# S7_SDRAM.net
KiCad netlist of a schematic drawn in Altium Designer
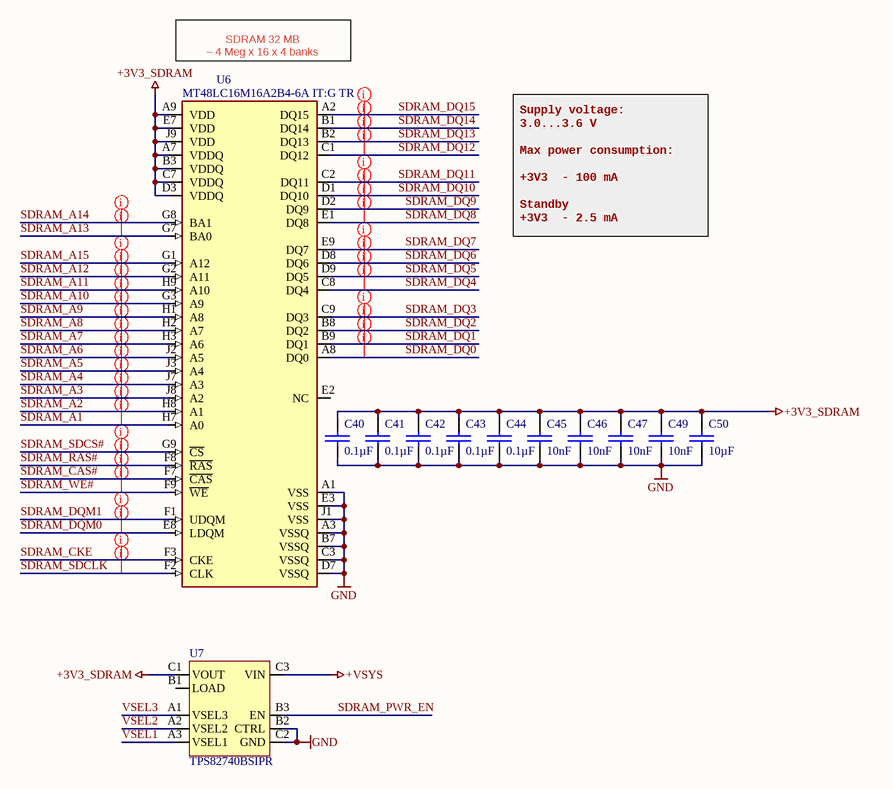
[diagram p0: S7_SDRAM.SchDoc]

(export (version "E")
  (design (tool "Eeschema 10.0.6"))
  (components
    (comp (ref "C40")
      (value "0.1µF")
      (footprint "0402 CAP")
      (description "0.1µF, ±10%, 50V, X7R, 0402 (1005 Metric), -55°C ~ 125°C, -, General Purpose")
      (fields
        (field (name "PART NUMBER") "0402B104K500CT")
        (field (name "MANUFACTURER") "Walsin Technology Corporation")
      )
      (libsource (lib "ea_PassivComps") (part "Capacitor"))
    )
    (comp (ref "C41")
      (value "0.1µF")
      (footprint "0402 CAP")
      (description "0.1µF, ±10%, 50V, X7R, 0402 (1005 Metric), -55°C ~ 125°C, -, General Purpose")
      (fields
        (field (name "PART NUMBER") "0402B104K500CT")
        (field (name "MANUFACTURER") "Walsin Technology Corporation")
      )
      (libsource (lib "ea_PassivComps") (part "Capacitor"))
    )
    (comp (ref "C42")
      (value "0.1µF")
      (footprint "0402 CAP")
      (description "0.1µF, ±10%, 50V, X7R, 0402 (1005 Metric), -55°C ~ 125°C, -, General Purpose")
      (fields
        (field (name "PART NUMBER") "0402B104K500CT")
        (field (name "MANUFACTURER") "Walsin Technology Corporation")
      )
      (libsource (lib "ea_PassivComps") (part "Capacitor"))
    )
    (comp (ref "C43")
      (value "0.1µF")
      (footprint "0402 CAP")
      (description "0.1µF, ±10%, 50V, X7R, 0402 (1005 Metric), -55°C ~ 125°C, -, General Purpose")
      (fields
        (field (name "PART NUMBER") "0402B104K500CT")
        (field (name "MANUFACTURER") "Walsin Technology Corporation")
      )
      (libsource (lib "ea_PassivComps") (part "Capacitor"))
    )
    (comp (ref "C44")
      (value "0.1µF")
      (footprint "0402 CAP")
      (description "0.1µF, ±10%, 50V, X7R, 0402 (1005 Metric), -55°C ~ 125°C, -, General Purpose")
      (fields
        (field (name "PART NUMBER") "0402B104K500CT")
        (field (name "MANUFACTURER") "Walsin Technology Corporation")
      )
      (libsource (lib "ea_PassivComps") (part "Capacitor"))
    )
    (comp (ref "C45")
      (value "10nF")
      (footprint "0402 CAP")
      (description "10000pF, ±10%, 50V, X7R, 0402 (1005 Metric), -55°C ~ 125°C, -, General Purpose")
      (fields
        (field (name "PART NUMBER") "CL05B103KB5NNNC")
        (field (name "MANUFACTURER") "Samsung Electro-Mechanics")
      )
      (libsource (lib "ea_PassivComps") (part "Capacitor"))
    )
    (comp (ref "C46")
      (value "10nF")
      (footprint "0402 CAP")
      (description "10000pF, ±10%, 50V, X7R, 0402 (1005 Metric), -55°C ~ 125°C, -, General Purpose")
      (fields
        (field (name "PART NUMBER") "CL05B103KB5NNNC")
        (field (name "MANUFACTURER") "Samsung Electro-Mechanics")
      )
      (libsource (lib "ea_PassivComps") (part "Capacitor"))
    )
    (comp (ref "C47")
      (value "10nF")
      (footprint "0402 CAP")
      (description "10000pF, ±10%, 50V, X7R, 0402 (1005 Metric), -55°C ~ 125°C, -, General Purpose")
      (fields
        (field (name "PART NUMBER") "CL05B103KB5NNNC")
        (field (name "MANUFACTURER") "Samsung Electro-Mechanics")
      )
      (libsource (lib "ea_PassivComps") (part "Capacitor"))
    )
    (comp (ref "C49")
      (value "10nF")
      (footprint "0402 CAP")
      (description "10000pF, ±10%, 50V, X7R, 0402 (1005 Metric), -55°C ~ 125°C, -, General Purpose")
      (fields
        (field (name "PART NUMBER") "CL05B103KB5NNNC")
        (field (name "MANUFACTURER") "Samsung Electro-Mechanics")
      )
      (libsource (lib "ea_PassivComps") (part "Capacitor"))
    )
    (comp (ref "C50")
      (value "10µF")
      (footprint "0603 CAP")
      (description "10µF, ±10%, 16V, X5R, 0603 (1608 Metric), -55°C ~ 85°C, -, Automotive")
      (fields
        (field (name "PART NUMBER") "GRT188R61C106KE13D")
        (field (name "MANUFACTURER") "Murata Electronics North America")
      )
      (libsource (lib "ea_PassivComps") (part "Capacitor"))
    )
    (comp (ref "U6")
      (value "MT48LC16M16A2B4-6A IT:G TR")
      (footprint "MICRON_VFBGA54")
      (description "Micron SDRAM 256M-Bit 16Mx16, 3.3V, 167MHz, 6ns, -40°C ~ +85°C, 54-VFBGA (8x8) Pb-free")
      (fields
        (field (name "MANUFACTURER") "Micron Technology Inc.")
        (field (name "PARTNUM") "340-128306-REEL")
      )
      (libsource (lib "ea_IC_RAM") (part "MT48LC16M16A2B4-6A IT{colon}G TR"))
    )
    (comp (ref "U7")
      (value "TPS82740BSIPR")
      (footprint "MicroSiP")
      (fields (field (name "MANUFACTURER") "Texas Instruments") (field (name "PARTNUM") "296-46481-1-ND"))
      (libsource (lib "ea_IC_Power_Reg_Ref_Sw") (part "TPS82740BSIPR"))
    )
  )
  (nets
    (net (code "1") (name "+3V3_SDRAM") (class "Default")
      (node (ref "C40") (pin "1") (pinfunction "1_1") (pintype "passive"))
      (node (ref "C41") (pin "1") (pinfunction "1_1") (pintype "passive"))
      (node (ref "C42") (pin "1") (pinfunction "1_1") (pintype "passive"))
      (node (ref "C43") (pin "1") (pinfunction "1_1") (pintype "passive"))
      (node (ref "C44") (pin "1") (pinfunction "1_1") (pintype "passive"))
      (node (ref "C45") (pin "1") (pinfunction "1_1") (pintype "passive"))
      (node (ref "C46") (pin "1") (pinfunction "1_1") (pintype "passive"))
      (node (ref "C47") (pin "1") (pinfunction "1_1") (pintype "passive"))
      (node (ref "C49") (pin "1") (pinfunction "1_1") (pintype "passive"))
      (node (ref "C50") (pin "1") (pinfunction "1_1") (pintype "passive"))
      (node (ref "U6") (pin "A7") (pinfunction "VDDQ_A7") (pintype "power_in"))
      (node (ref "U6") (pin "A9") (pinfunction "VDD_A9") (pintype "power_in"))
      (node (ref "U6") (pin "B3") (pinfunction "VDDQ_B3") (pintype "power_in"))
      (node (ref "U6") (pin "C7") (pinfunction "VDDQ_C7") (pintype "power_in"))
      (node (ref "U6") (pin "D3") (pinfunction "VDDQ_D3") (pintype "power_in"))
      (node (ref "U6") (pin "E7") (pinfunction "VDD_E7") (pintype "power_in"))
      (node (ref "U6") (pin "J9") (pinfunction "VDD_J9") (pintype "power_in"))
      (node (ref "U7") (pin "C1") (pinfunction "VOUT_C1") (pintype "passive"))
    )
    (net (code "2") (name "+VSYS") (class "Default")
      (node (ref "U7") (pin "C3") (pinfunction "VIN_C3") (pintype "passive"))
    )
    (net (code "3") (name "/SDRAM_A1") (class "Default")
      (node (ref "U6") (pin "H7") (pinfunction "A0_H7") (pintype "input"))
    )
    (net (code "4") (name "/SDRAM_A2") (class "Default")
      (node (ref "U6") (pin "H8") (pinfunction "A1_H8") (pintype "input"))
    )
    (net (code "5") (name "/SDRAM_A3") (class "Default")
      (node (ref "U6") (pin "J8") (pinfunction "A2_J8") (pintype "input"))
    )
    (net (code "6") (name "/SDRAM_A4") (class "Default")
      (node (ref "U6") (pin "J7") (pinfunction "A3_J7") (pintype "input"))
    )
    (net (code "7") (name "/SDRAM_A5") (class "Default")
      (node (ref "U6") (pin "J3") (pinfunction "A4_J3") (pintype "input"))
    )
    (net (code "8") (name "/SDRAM_A6") (class "Default")
      (node (ref "U6") (pin "J2") (pinfunction "A5_J2") (pintype "input"))
    )
    (net (code "9") (name "/SDRAM_A7") (class "Default")
      (node (ref "U6") (pin "H3") (pinfunction "A6_H3") (pintype "input"))
    )
    (net (code "10") (name "/SDRAM_A8") (class "Default")
      (node (ref "U6") (pin "H2") (pinfunction "A7_H2") (pintype "input"))
    )
    (net (code "11") (name "/SDRAM_A9") (class "Default")
      (node (ref "U6") (pin "H1") (pinfunction "A8_H1") (pintype "input"))
    )
    (net (code "12") (name "/SDRAM_A10") (class "Default")
      (node (ref "U6") (pin "G3") (pinfunction "A9_G3") (pintype "input"))
    )
    (net (code "13") (name "/SDRAM_A11") (class "Default")
      (node (ref "U6") (pin "H9") (pinfunction "A10_H9") (pintype "input"))
    )
    (net (code "14") (name "/SDRAM_A12") (class "Default")
      (node (ref "U6") (pin "G2") (pinfunction "A11_G2") (pintype "input"))
    )
    (net (code "15") (name "/SDRAM_A13") (class "Default")
      (node (ref "U6") (pin "G7") (pinfunction "BA0_G7") (pintype "input"))
    )
    (net (code "16") (name "/SDRAM_A14") (class "Default")
      (node (ref "U6") (pin "G8") (pinfunction "BA1_G8") (pintype "input"))
    )
    (net (code "17") (name "/SDRAM_A15") (class "Default")
      (node (ref "U6") (pin "G1") (pinfunction "A12_G1") (pintype "input"))
    )
    (net (code "18") (name "/SDRAM_CAS#") (class "Default")
      (node (ref "U6") (pin "F7") (pinfunction "~{CAS}_F7") (pintype "input"))
    )
    (net (code "19") (name "/SDRAM_CKE") (class "Default")
      (node (ref "U6") (pin "F3") (pinfunction "CKE_F3") (pintype "input"))
    )
    (net (code "20") (name "/SDRAM_DQ0") (class "Default")
      (node (ref "U6") (pin "A8") (pinfunction "DQ0_A8") (pintype "bidirectional"))
    )
    (net (code "21") (name "/SDRAM_DQ1") (class "Default")
      (node (ref "U6") (pin "B9") (pinfunction "DQ1_B9") (pintype "bidirectional"))
    )
    (net (code "22") (name "/SDRAM_DQ2") (class "Default")
      (node (ref "U6") (pin "B8") (pinfunction "DQ2_B8") (pintype "bidirectional"))
    )
    (net (code "23") (name "/SDRAM_DQ3") (class "Default")
      (node (ref "U6") (pin "C9") (pinfunction "DQ3_C9") (pintype "bidirectional"))
    )
    (net (code "24") (name "/SDRAM_DQ4") (class "Default")
      (node (ref "U6") (pin "C8") (pinfunction "DQ4_C8") (pintype "bidirectional"))
    )
    (net (code "25") (name "/SDRAM_DQ5") (class "Default")
      (node (ref "U6") (pin "D9") (pinfunction "DQ5_D9") (pintype "bidirectional"))
    )
    (net (code "26") (name "/SDRAM_DQ6") (class "Default")
      (node (ref "U6") (pin "D8") (pinfunction "DQ6_D8") (pintype "bidirectional"))
    )
    (net (code "27") (name "/SDRAM_DQ7") (class "Default")
      (node (ref "U6") (pin "E9") (pinfunction "DQ7_E9") (pintype "bidirectional"))
    )
    (net (code "28") (name "/SDRAM_DQ8") (class "Default")
      (node (ref "U6") (pin "E1") (pinfunction "DQ8_E1") (pintype "bidirectional"))
    )
    (net (code "29") (name "/SDRAM_DQ9") (class "Default")
      (node (ref "U6") (pin "D2") (pinfunction "DQ9_D2") (pintype "bidirectional"))
    )
    (net (code "30") (name "/SDRAM_DQ10") (class "Default")
      (node (ref "U6") (pin "D1") (pinfunction "DQ10_D1") (pintype "bidirectional"))
    )
    (net (code "31") (name "/SDRAM_DQ11") (class "Default")
      (node (ref "U6") (pin "C2") (pinfunction "DQ11_C2") (pintype "bidirectional"))
    )
    (net (code "32") (name "/SDRAM_DQ12") (class "Default")
      (node (ref "U6") (pin "C1") (pinfunction "DQ12_C1") (pintype "bidirectional"))
    )
    (net (code "33") (name "/SDRAM_DQ13") (class "Default")
      (node (ref "U6") (pin "B2") (pinfunction "DQ13_B2") (pintype "bidirectional"))
    )
    (net (code "34") (name "/SDRAM_DQ14") (class "Default")
      (node (ref "U6") (pin "B1") (pinfunction "DQ14_B1") (pintype "bidirectional"))
    )
    (net (code "35") (name "/SDRAM_DQ15") (class "Default")
      (node (ref "U6") (pin "A2") (pinfunction "DQ15_A2") (pintype "bidirectional"))
    )
    (net (code "36") (name "/SDRAM_DQM0") (class "Default")
      (node (ref "U6") (pin "E8") (pinfunction "LDQM_E8") (pintype "input"))
    )
    (net (code "37") (name "/SDRAM_DQM1") (class "Default")
      (node (ref "U6") (pin "F1") (pinfunction "UDQM_F1") (pintype "input"))
    )
    (net (code "38") (name "/SDRAM_PWR_EN") (class "Default")
      (node (ref "U7") (pin "B3") (pinfunction "EN_B3") (pintype "passive"))
    )
    (net (code "39") (name "/SDRAM_RAS#") (class "Default")
      (node (ref "U6") (pin "F8") (pinfunction "~{RAS}_F8") (pintype "input"))
    )
    (net (code "40") (name "/SDRAM_SDCLK") (class "Default")
      (node (ref "U6") (pin "F2") (pinfunction "CLK_F2") (pintype "input"))
    )
    (net (code "41") (name "/SDRAM_SDCS#") (class "Default")
      (node (ref "U6") (pin "G9") (pinfunction "~{CS}_G9") (pintype "input"))
    )
    (net (code "42") (name "/SDRAM_WE#") (class "Default")
      (node (ref "U6") (pin "F9") (pinfunction "~{WE}_F9") (pintype "input"))
    )
    (net (code "43") (name "/VSEL1") (class "Default")
      (node (ref "U7") (pin "A3") (pinfunction "VSEL1_A3") (pintype "passive"))
    )
    (net (code "44") (name "/VSEL2") (class "Default")
      (node (ref "U7") (pin "A2") (pinfunction "VSEL2_A2") (pintype "passive"))
    )
    (net (code "45") (name "/VSEL3") (class "Default")
      (node (ref "U7") (pin "A1") (pinfunction "VSEL3_A1") (pintype "passive"))
    )
    (net (code "46") (name "GND") (class "Default")
      (node (ref "C40") (pin "2") (pinfunction "2_2") (pintype "passive"))
      (node (ref "C41") (pin "2") (pinfunction "2_2") (pintype "passive"))
      (node (ref "C42") (pin "2") (pinfunction "2_2") (pintype "passive"))
      (node (ref "C43") (pin "2") (pinfunction "2_2") (pintype "passive"))
      (node (ref "C44") (pin "2") (pinfunction "2_2") (pintype "passive"))
      (node (ref "C45") (pin "2") (pinfunction "2_2") (pintype "passive"))
      (node (ref "C46") (pin "2") (pinfunction "2_2") (pintype "passive"))
      (node (ref "C47") (pin "2") (pinfunction "2_2") (pintype "passive"))
      (node (ref "C49") (pin "2") (pinfunction "2_2") (pintype "passive"))
      (node (ref "C50") (pin "2") (pinfunction "2_2") (pintype "passive"))
      (node (ref "U6") (pin "A1") (pinfunction "VSS_A1") (pintype "power_in"))
      (node (ref "U6") (pin "A3") (pinfunction "VSSQ_A3") (pintype "power_in"))
      (node (ref "U6") (pin "B7") (pinfunction "VSSQ_B7") (pintype "power_in"))
      (node (ref "U6") (pin "C3") (pinfunction "VSSQ_C3") (pintype "power_in"))
      (node (ref "U6") (pin "D7") (pinfunction "VSSQ_D7") (pintype "power_in"))
      (node (ref "U6") (pin "E3") (pinfunction "VSS_E3") (pintype "power_in"))
      (node (ref "U6") (pin "J1") (pinfunction "VSS_J1") (pintype "power_in"))
      (node (ref "U7") (pin "B2") (pinfunction "CTRL_B2") (pintype "passive"))
      (node (ref "U7") (pin "C2") (pinfunction "GND_C2") (pintype "passive"))
    )
    (net (code "47") (name "unconnected-(U6-NC-PadE2)") (class "Default")
      (node (ref "U6") (pin "E2") (pinfunction "NC_E2") (pintype "passive"))
    )
    (net (code "48") (name "unconnected-(U7-LOAD-PadB1)") (class "Default")
      (node (ref "U7") (pin "B1") (pinfunction "LOAD_B1") (pintype "passive"))
    )
  )
)
